# 07_EL_CON.net
KiCad netlist of a schematic drawn in Altium Designer
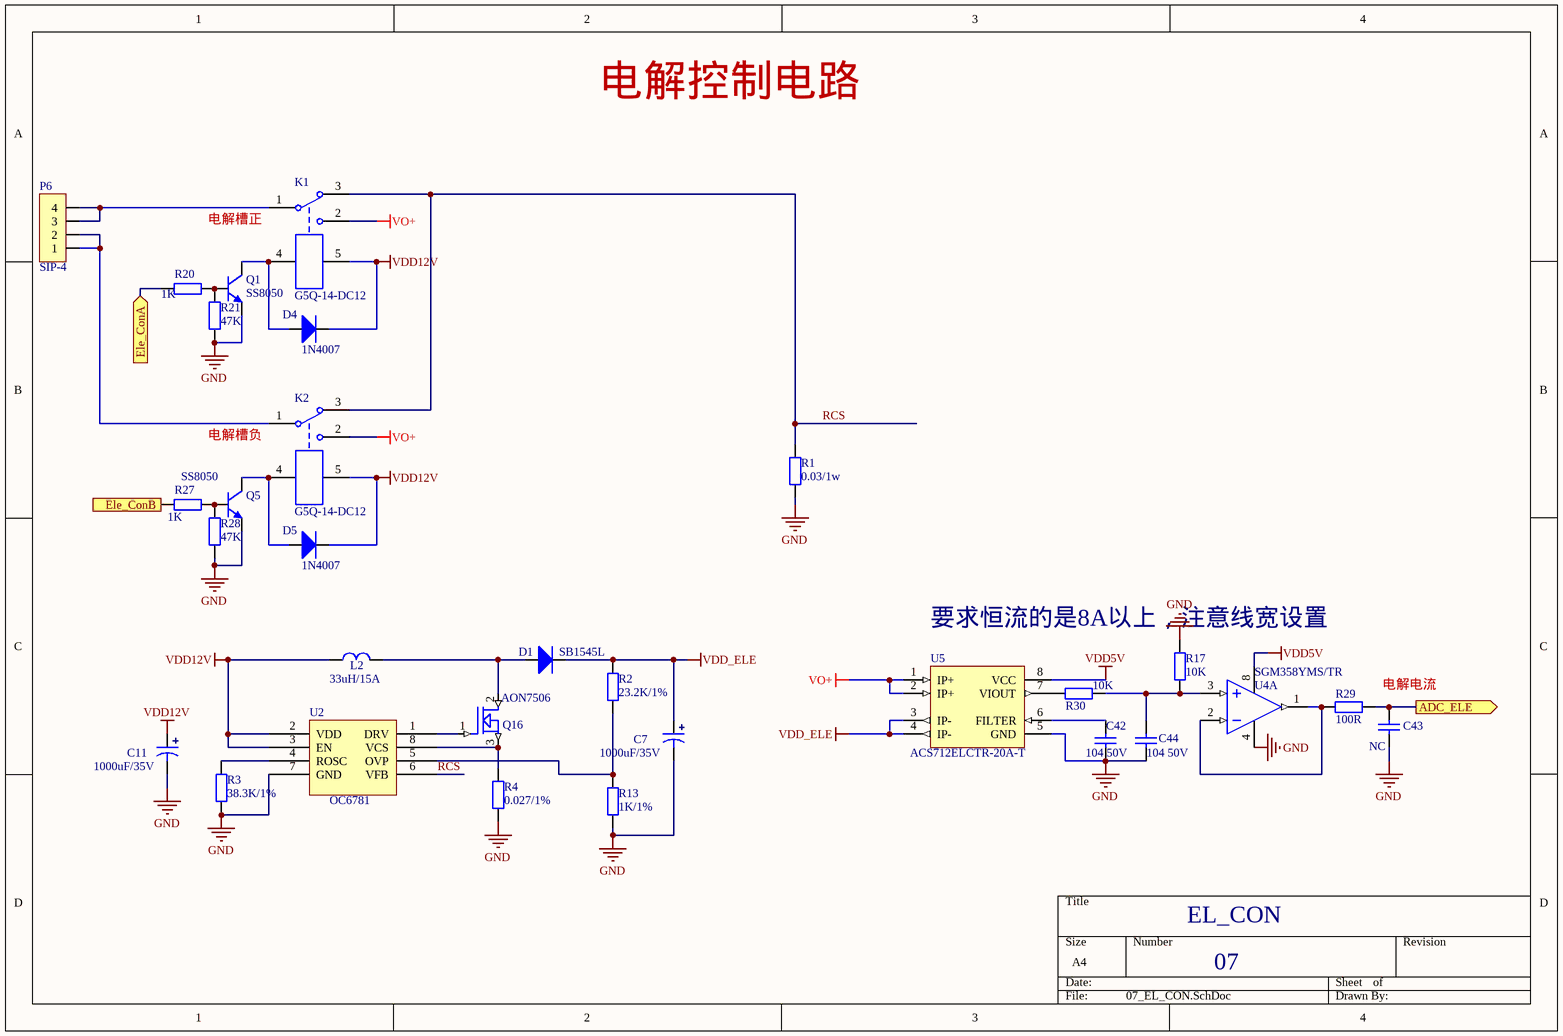
[diagram p0: 07_EL_CON.SchDoc]

(export (version "E")
  (design (tool "Eeschema 10.0.6"))
  (components
    (comp (ref "C7")
      (value "1000uF/35V")
      (footprint "10*16")
      (description "电解电容")
      (libsource (lib "XiaoyI") (part "CAP2"))
    )
    (comp (ref "C11")
      (value "1000uF/35V")
      (footprint "10*16")
      (description "电解电容")
      (libsource (lib "XiaoyI") (part "CAP2"))
    )
    (comp (ref "C42")
      (value "104 50V")
      (footprint "SMD-0603C")
      (description "贴片电容 10%")
      (libsource (lib "XiaoyI") (part "CAP4"))
    )
    (comp (ref "C43")
      (value "NC")
      (footprint "SMD-0603C")
      (description "贴片电容 10%")
      (libsource (lib "XiaoyI") (part "CAP4"))
    )
    (comp (ref "C44")
      (value "104 50V")
      (footprint "SMD-0603C")
      (description "贴片电容 10%")
      (libsource (lib "XiaoyI") (part "CAP4"))
    )
    (comp (ref "D1")
      (value "SB1545L")
      (footprint "TO227")
      (description "肖特基二极管")
      (libsource (lib "XiaoyI") (part "DIODE2"))
    )
    (comp (ref "D4")
      (value "1N4007")
      (footprint "DO-214-AC")
      (description "贴片二极管")
      (libsource (lib "XiaoyI") (part "DIODE2"))
    )
    (comp (ref "D5")
      (value "1N4007")
      (footprint "DO-214-AC")
      (description "贴片二极管")
      (libsource (lib "XiaoyI") (part "DIODE2"))
    )
    (comp (ref "K1")
      (value "G5Q-14-DC12")
      (footprint "G5Q-14")
      (description "5V 继电器")
      (libsource (lib "XiaoyI") (part "JDQ1"))
    )
    (comp (ref "K2")
      (value "G5Q-14-DC12")
      (footprint "G5Q-14")
      (description "5V 继电器")
      (libsource (lib "XiaoyI") (part "JDQ1"))
    )
    (comp (ref "L2")
      (value "33uH/15A")
      (footprint "INDUCTOR_34*18")
      (description "10uH 1A")
      (libsource (lib "XiaoyI") (part "Inductor1"))
    )
    (comp (ref "P6")
      (value "SIP-4")
      (footprint "VH-AW-3.96*4P")
      (description "3.96 4P 直插")
      (libsource (lib "XiaoyI") (part "SIP-4"))
    )
    (comp (ref "Q1")
      (value "SS8050")
      (footprint "SOT-23")
      (description "三极管")
      (libsource (lib "XiaoyI") (part "NPN-1"))
    )
    (comp (ref "Q5")
      (value "SS8050")
      (footprint "SOT-23")
      (description "三极管")
      (libsource (lib "XiaoyI") (part "NPN-1"))
    )
    (comp (ref "Q16")
      (value "AON7506")
      (footprint "DFN3*3-8")
      (description "MOSFET N")
      (libsource (lib "XiaoyI") (part "MOSFET N"))
    )
    (comp (ref "R1")
      (value "0.03/1w")
      (footprint "2512R")
      (description "贴片电阻 5%")
      (libsource (lib "") (part "RES2_2"))
    )
    (comp (ref "R2")
      (value "23.2K/1%")
      (footprint "SMD-0603")
      (description "贴片电阻 5%")
      (libsource (lib "") (part "RES2_2"))
    )
    (comp (ref "R3")
      (value "38.3K/1%")
      (footprint "SMD-0603")
      (description "贴片电阻 5%")
      (libsource (lib "") (part "RES2_2"))
    )
    (comp (ref "R4")
      (value "0.027/1%")
      (footprint "2512r")
      (description "贴片电阻 5%")
      (libsource (lib "") (part "RES2_2"))
    )
    (comp (ref "R13")
      (value "1K/1%")
      (footprint "SMD-0603")
      (description "贴片电阻 5%")
      (libsource (lib "") (part "RES2_2"))
    )
    (comp (ref "R17")
      (value "10K")
      (footprint "SMD-0603")
      (description "贴片电阻 1%")
      (libsource (lib "") (part "RES0_1"))
    )
    (comp (ref "R20")
      (value "1K")
      (footprint "SMD-0603")
      (description "贴片电阻 5%")
      (libsource (lib "XiaoyI") (part "RES2"))
    )
    (comp (ref "R21")
      (value "47K")
      (footprint "SMD-0603")
      (description "贴片电阻 5%")
      (libsource (lib "") (part "RES2_1"))
    )
    (comp (ref "R27")
      (value "1K")
      (footprint "SMD-0603")
      (description "贴片电阻 5%")
      (libsource (lib "XiaoyI") (part "RES2"))
    )
    (comp (ref "R28")
      (value "47K")
      (footprint "SMD-0603")
      (description "贴片电阻 5%")
      (libsource (lib "") (part "RES2_1"))
    )
    (comp (ref "R29")
      (value "100R")
      (footprint "SMD-0603")
      (description "贴片电阻 5%")
      (libsource (lib "ABB") (part "RES0"))
    )
    (comp (ref "R30")
      (value "10K")
      (footprint "SMD-0603")
      (description "贴片电阻 1%")
      (libsource (lib "ABB") (part "RES0"))
    )
    (comp (ref "U2")
      (value "OC6781")
      (footprint "SOP127P600X265_HS-9N")
      (libsource (lib "stm32") (part "OC6781"))
    )
    (comp (ref "U4")
      (value "SGM358YMS/TR")
      (footprint "MSOP-8")
      (description "运算放大器")
      (libsource (lib "XiaoyI") (part "LM358"))
    )
    (comp (ref "U5")
      (value "ACS712ELCTR-20A-T")
      (footprint "SO-8")
      (description "HALL 20A 电流传感器")
      (libsource (lib "XiaoyI") (part "ACS712"))
    )
  )
  (nets
    (net (code "1") (name "/ADC_ELE") (class "Default")
      (node (ref "C43") (pin "2") (pinfunction "2_2") (pintype "passive"))
      (node (ref "R29") (pin "1") (pinfunction "1_1") (pintype "passive"))
    )
    (net (code "2") (name "/Ele_ConA") (class "Default")
      (node (ref "R20") (pin "1") (pinfunction "1_1") (pintype "passive"))
    )
    (net (code "3") (name "/Ele_ConB") (class "Default")
      (node (ref "R27") (pin "1") (pinfunction "1_1") (pintype "passive"))
    )
    (net (code "4") (name "/RCS") (class "Default")
      (node (ref "K1") (pin "3") (pinfunction "3_3") (pintype "passive"))
      (node (ref "K2") (pin "3") (pinfunction "3_3") (pintype "passive"))
      (node (ref "R1") (pin "1") (pinfunction "1_1") (pintype "passive"))
      (node (ref "U2") (pin "6") (pinfunction "VFB_6") (pintype "passive"))
    )
    (net (code "5") (name "GND") (class "Default")
      (node (ref "C11") (pin "2") (pinfunction "2_2") (pintype "passive"))
      (node (ref "C42") (pin "2") (pinfunction "2_2") (pintype "passive"))
      (node (ref "C43") (pin "1") (pinfunction "1_1") (pintype "passive"))
      (node (ref "C44") (pin "2") (pinfunction "2_2") (pintype "passive"))
      (node (ref "C7") (pin "2") (pinfunction "2_2") (pintype "passive"))
      (node (ref "Q1") (pin "2") (pinfunction "E_2") (pintype "passive"))
      (node (ref "Q5") (pin "2") (pinfunction "E_2") (pintype "passive"))
      (node (ref "R1") (pin "2") (pinfunction "2_2") (pintype "passive"))
      (node (ref "R13") (pin "2") (pinfunction "2_2") (pintype "passive"))
      (node (ref "R17") (pin "1") (pinfunction "1_1") (pintype "passive"))
      (node (ref "R21") (pin "1") (pinfunction "1_1") (pintype "passive"))
      (node (ref "R28") (pin "1") (pinfunction "1_1") (pintype "passive"))
      (node (ref "R3") (pin "2") (pinfunction "2_2") (pintype "passive"))
      (node (ref "R4") (pin "2") (pinfunction "2_2") (pintype "passive"))
      (node (ref "U2") (pin "7") (pinfunction "GND_7") (pintype "passive"))
      (node (ref "U4") (pin "4") (pinfunction "V-_4") (pintype "power_in"))
      (node (ref "U5") (pin "5") (pinfunction "GND_5") (pintype "power_in"))
    )
    (net (code "6") (name "Net-(D1-A)") (class "Default")
      (node (ref "D1") (pin "1") (pinfunction "A_1") (pintype "passive"))
      (node (ref "L2") (pin "2") (pinfunction "2_2") (pintype "passive"))
      (node (ref "Q16") (pin "2") (pinfunction "D_2") (pintype "input"))
    )
    (net (code "7") (name "Net-(D4-A)") (class "Default")
      (node (ref "D4") (pin "1") (pinfunction "A_1") (pintype "passive"))
      (node (ref "K1") (pin "4") (pinfunction "4_4") (pintype "passive"))
      (node (ref "Q1") (pin "3") (pinfunction "C_3") (pintype "passive"))
    )
    (net (code "8") (name "Net-(D5-A)") (class "Default")
      (node (ref "D5") (pin "1") (pinfunction "A_1") (pintype "passive"))
      (node (ref "K2") (pin "4") (pinfunction "4_4") (pintype "passive"))
      (node (ref "Q5") (pin "3") (pinfunction "C_3") (pintype "passive"))
    )
    (net (code "9") (name "Net-(K1-Pad1)") (class "Default")
      (node (ref "K1") (pin "1") (pinfunction "1_1") (pintype "passive"))
      (node (ref "P6") (pin "3") (pinfunction "3_3") (pintype "passive"))
      (node (ref "P6") (pin "4") (pinfunction "4_4") (pintype "passive"))
    )
    (net (code "10") (name "Net-(K2-Pad1)") (class "Default")
      (node (ref "K2") (pin "1") (pinfunction "1_1") (pintype "passive"))
      (node (ref "P6") (pin "1") (pinfunction "1_1") (pintype "passive"))
      (node (ref "P6") (pin "2") (pinfunction "2_2") (pintype "passive"))
    )
    (net (code "11") (name "Net-(Q1-B)") (class "Default")
      (node (ref "Q1") (pin "1") (pinfunction "B_1") (pintype "passive"))
      (node (ref "R20") (pin "2") (pinfunction "2_2") (pintype "passive"))
      (node (ref "R21") (pin "2") (pinfunction "2_2") (pintype "passive"))
    )
    (net (code "12") (name "Net-(Q5-B)") (class "Default")
      (node (ref "Q5") (pin "1") (pinfunction "B_1") (pintype "passive"))
      (node (ref "R27") (pin "2") (pinfunction "2_2") (pintype "passive"))
      (node (ref "R28") (pin "2") (pinfunction "2_2") (pintype "passive"))
    )
    (net (code "13") (name "Net-(Q16-G)") (class "Default")
      (node (ref "Q16") (pin "1") (pinfunction "G_1") (pintype "input"))
      (node (ref "U2") (pin "1") (pinfunction "DRV_1") (pintype "passive"))
    )
    (net (code "14") (name "Net-(Q16-S)") (class "Default")
      (node (ref "Q16") (pin "3") (pinfunction "S_3") (pintype "output"))
      (node (ref "R4") (pin "1") (pinfunction "1_1") (pintype "passive"))
      (node (ref "U2") (pin "8") (pinfunction "VCS_8") (pintype "passive"))
    )
    (net (code "15") (name "Net-(U2-OVP)") (class "Default")
      (node (ref "R13") (pin "1") (pinfunction "1_1") (pintype "passive"))
      (node (ref "R2") (pin "2") (pinfunction "2_2") (pintype "passive"))
      (node (ref "U2") (pin "5") (pinfunction "OVP_5") (pintype "passive"))
    )
    (net (code "16") (name "Net-(U2-ROSC)") (class "Default")
      (node (ref "R3") (pin "1") (pinfunction "1_1") (pintype "passive"))
      (node (ref "U2") (pin "4") (pinfunction "ROSC_4") (pintype "passive"))
    )
    (net (code "17") (name "Net-(U4A-IN1+)") (class "Default")
      (node (ref "C44") (pin "1") (pinfunction "1_1") (pintype "passive"))
      (node (ref "R17") (pin "2") (pinfunction "2_2") (pintype "passive"))
      (node (ref "R30") (pin "1") (pinfunction "1_1") (pintype "passive"))
      (node (ref "U4") (pin "3") (pinfunction "IN1+_3") (pintype "input"))
    )
    (net (code "18") (name "Net-(U4A-IN1-)") (class "Default")
      (node (ref "R29") (pin "2") (pinfunction "2_2") (pintype "passive"))
      (node (ref "U4") (pin "1") (pinfunction "OUT1_1") (pintype "output"))
      (node (ref "U4") (pin "2") (pinfunction "IN1-_2") (pintype "input"))
    )
    (net (code "19") (name "Net-(U5-FILTER)") (class "Default")
      (node (ref "C42") (pin "1") (pinfunction "1_1") (pintype "passive"))
      (node (ref "U5") (pin "6") (pinfunction "FILTER_6") (pintype "input"))
    )
    (net (code "20") (name "Net-(U5-VIOUT)") (class "Default")
      (node (ref "R30") (pin "2") (pinfunction "2_2") (pintype "passive"))
      (node (ref "U5") (pin "7") (pinfunction "VIOUT_7") (pintype "output"))
    )
    (net (code "21") (name "VDD5V") (class "Default")
      (node (ref "U4") (pin "8") (pinfunction "V+_8") (pintype "power_in"))
      (node (ref "U5") (pin "8") (pinfunction "VCC_8") (pintype "power_in"))
    )
    (net (code "22") (name "VDD12V") (class "Default")
      (node (ref "C11") (pin "1") (pinfunction "1_1") (pintype "passive"))
      (node (ref "D4") (pin "2") (pinfunction "K_2") (pintype "passive"))
      (node (ref "D5") (pin "2") (pinfunction "K_2") (pintype "passive"))
      (node (ref "K1") (pin "5") (pinfunction "5_5") (pintype "passive"))
      (node (ref "K2") (pin "5") (pinfunction "5_5") (pintype "passive"))
      (node (ref "L2") (pin "1") (pinfunction "1_1") (pintype "passive"))
      (node (ref "U2") (pin "2") (pinfunction "VDD_2") (pintype "passive"))
      (node (ref "U2") (pin "3") (pinfunction "EN_3") (pintype "passive"))
    )
    (net (code "23") (name "VDD_ELE") (class "Default")
      (node (ref "C7") (pin "1") (pinfunction "1_1") (pintype "passive"))
      (node (ref "D1") (pin "2") (pinfunction "K_2") (pintype "passive"))
      (node (ref "R2") (pin "1") (pinfunction "1_1") (pintype "passive"))
      (node (ref "U5") (pin "3") (pinfunction "IP-_3") (pintype "output"))
      (node (ref "U5") (pin "4") (pinfunction "IP-_4") (pintype "output"))
    )
    (net (code "24") (name "VO+") (class "Default")
      (node (ref "K1") (pin "2") (pinfunction "2_2") (pintype "passive"))
      (node (ref "K2") (pin "2") (pinfunction "2_2") (pintype "passive"))
      (node (ref "U5") (pin "1") (pinfunction "IP+_1") (pintype "input"))
      (node (ref "U5") (pin "2") (pinfunction "IP+_2") (pintype "input"))
    )
  )
)
